# ElectricalDesign.net
KiCad netlist of a schematic drawn in Altium Designer
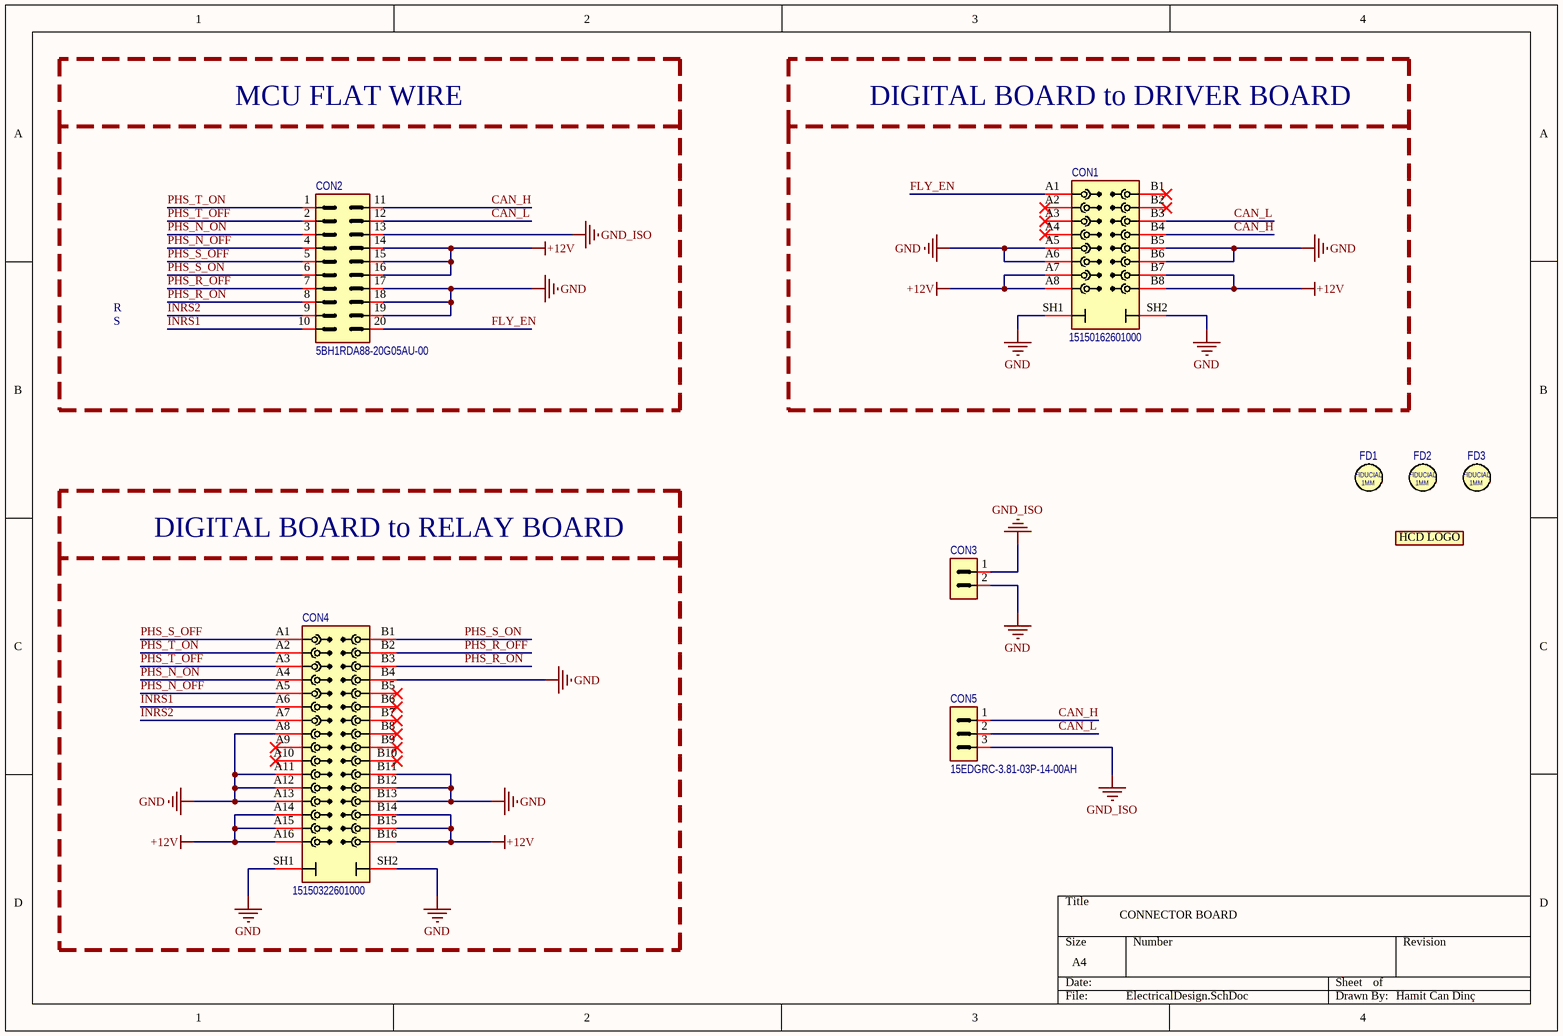
[diagram p0: ElectricalDesign.SchDoc]

(export (version "E")
  (design (tool "Eeschema 10.0.6"))
  (components
    (comp (ref "CON1")
      (value "CON_16P_2R_A8-B8_2SH")
      (footprint "CON_15150162601000_HARTING")
      (description "Connector Header Surface Mount, Right Angle 16 position 0.050\" (1.27mm)")
      (fields (field (name "MANUFACTURER PN") "15150162601000") (field (name "MANUFACTURER") "HARTING"))
      (libsource (lib "HCD_Database_Libs") (part "CON_16P_2R_A8-B8_2SH"))
    )
    (comp (ref "CON2")
      (value "CON_20POS_2R")
      (footprint "male-thd-box-header-2x10-2.54mm-90D_AMTEK")
      (description "BOX HEADER 20PIN(2x10) 2.54mm THT R/A MALE BLACK")
      (fields
        (field (name "MANUFACTURER PN") "5BH1RDA88-20G05AU-00")
        (field (name "MANUFACTURER") "AMTEK")
        (field (name "VOLTAGE") "1000V AC")
      )
      (libsource (lib "HCD_Database_Libs") (part "CON_20POS_2R"))
    )
    (comp (ref "CON3")
      (value "CON_2POS_1R")
      (footprint "male-thd-1x2-pin-header-2.54mm-90D")
      (description "PIN HEADER 2PIN(1x2) 2.54mm THT R/A 6X3X4.5MM")
      (fields (field (name "MANUFACTURER") "AMTEK") (field (name "VOLTAGE") "500V AC"))
      (libsource (lib "HCD_Database_Libs") (part "CON_2POS_1R"))
    )
    (comp (ref "CON4")
      (value "CON_32P_2R_A16-B16_2SH")
      (footprint "CON_15150322601000_HARTING")
      (description "Connector Header Surface Mount, Right Angle 32 position 0.050\" (1.27mm)")
      (fields (field (name "MANUFACTURER PN") "15150322601000") (field (name "MANUFACTURER") "HARTING"))
      (libsource (lib "HCD_Database_Libs") (part "CON_32P_2R_A16-B16_2SH"))
    )
    (comp (ref "CON5")
      (value "CON_3POS_1R")
      (footprint "CON_15EDGRC-3.81-03P-14-00AH")
      (description "TERM.BLK.3.81MM 3P 90C MALE GREEN CLOSED")
      (fields
        (field (name "MANUFACTURER PN") "15EDGRC-3.81-03P-14-00AH")
        (field (name "MANUFACTURER") "DEGSON")
        (field (name "VOLTAGE") "300V")
      )
      (libsource (lib "HCD_Database_Libs") (part "CON_3POS_1R"))
    )
    (comp (ref "FD1")
      (value "FIDUCIAL")
      (footprint "FIDUCIAL_1mm")
      (description "Fiducial 1mm")
      (libsource (lib "HCD_Database_Libs") (part "FIDUCIAL"))
    )
    (comp (ref "FD2")
      (value "FIDUCIAL")
      (footprint "FIDUCIAL_1mm")
      (description "Fiducial 1mm")
      (libsource (lib "HCD_Database_Libs") (part "FIDUCIAL"))
    )
    (comp (ref "FD3")
      (value "FIDUCIAL")
      (footprint "FIDUCIAL_1mm")
      (description "Fiducial 1mm")
      (libsource (lib "HCD_Database_Libs") (part "FIDUCIAL"))
    )
    (comp (ref "LOGO1")
      (value "HCD_LOGO")
      (footprint "HCD_LOGO_V1")
      (description "Hamit Can Dinç LOGO")
      (libsource (lib "HCD_Database_Libs") (part "HCD_LOGO"))
    )
  )
  (nets
    (net (code "1") (name "+12V") (class "Default")
      (node (ref "CON1") (pin "A7") (pinfunction "A7_A7") (pintype "passive"))
      (node (ref "CON1") (pin "A8") (pinfunction "A8_A8") (pintype "passive"))
      (node (ref "CON1") (pin "B7") (pinfunction "B7_B7") (pintype "passive"))
      (node (ref "CON1") (pin "B8") (pinfunction "B8_B8") (pintype "passive"))
      (node (ref "CON2") (pin "14") (pinfunction "14_14") (pintype "passive"))
      (node (ref "CON2") (pin "15") (pinfunction "15_15") (pintype "passive"))
      (node (ref "CON2") (pin "16") (pinfunction "16_16") (pintype "passive"))
      (node (ref "CON4") (pin "A14") (pinfunction "A14_A14") (pintype "passive"))
      (node (ref "CON4") (pin "A15") (pinfunction "A15_A15") (pintype "passive"))
      (node (ref "CON4") (pin "A16") (pinfunction "A16_A16") (pintype "passive"))
      (node (ref "CON4") (pin "B14") (pinfunction "B14_B14") (pintype "passive"))
      (node (ref "CON4") (pin "B15") (pinfunction "B15_B15") (pintype "passive"))
      (node (ref "CON4") (pin "B16") (pinfunction "B16_B16") (pintype "passive"))
    )
    (net (code "2") (name "/CAN_H") (class "Default")
      (node (ref "CON1") (pin "B4") (pinfunction "B4_B4") (pintype "passive"))
      (node (ref "CON2") (pin "11") (pinfunction "11_11") (pintype "passive"))
      (node (ref "CON5") (pin "1") (pinfunction "1_1") (pintype "passive"))
    )
    (net (code "3") (name "/CAN_L") (class "Default")
      (node (ref "CON1") (pin "B3") (pinfunction "B3_B3") (pintype "passive"))
      (node (ref "CON2") (pin "12") (pinfunction "12_12") (pintype "passive"))
      (node (ref "CON5") (pin "2") (pinfunction "2_2") (pintype "passive"))
    )
    (net (code "4") (name "/FLY_EN") (class "Default")
      (node (ref "CON1") (pin "A1") (pinfunction "A1_A1") (pintype "passive"))
      (node (ref "CON2") (pin "20") (pinfunction "20_20") (pintype "passive"))
    )
    (net (code "5") (name "/INRS1") (class "Default")
      (node (ref "CON2") (pin "10") (pinfunction "10_10") (pintype "passive"))
      (node (ref "CON4") (pin "A6") (pinfunction "A6_A6") (pintype "passive"))
    )
    (net (code "6") (name "/INRS2") (class "Default")
      (node (ref "CON2") (pin "9") (pinfunction "9_9") (pintype "passive"))
      (node (ref "CON4") (pin "A7") (pinfunction "A7_A7") (pintype "passive"))
    )
    (net (code "7") (name "/PHS_N_OFF") (class "Default")
      (node (ref "CON2") (pin "4") (pinfunction "4_4") (pintype "passive"))
      (node (ref "CON4") (pin "A5") (pinfunction "A5_A5") (pintype "passive"))
    )
    (net (code "8") (name "/PHS_N_ON") (class "Default")
      (node (ref "CON2") (pin "3") (pinfunction "3_3") (pintype "passive"))
      (node (ref "CON4") (pin "A4") (pinfunction "A4_A4") (pintype "passive"))
    )
    (net (code "9") (name "/PHS_R_OFF") (class "Default")
      (node (ref "CON2") (pin "7") (pinfunction "7_7") (pintype "passive"))
      (node (ref "CON4") (pin "B2") (pinfunction "B2_B2") (pintype "passive"))
    )
    (net (code "10") (name "/PHS_R_ON") (class "Default")
      (node (ref "CON2") (pin "8") (pinfunction "8_8") (pintype "passive"))
      (node (ref "CON4") (pin "B3") (pinfunction "B3_B3") (pintype "passive"))
    )
    (net (code "11") (name "/PHS_S_OFF") (class "Default")
      (node (ref "CON2") (pin "5") (pinfunction "5_5") (pintype "passive"))
      (node (ref "CON4") (pin "A1") (pinfunction "A1_A1") (pintype "passive"))
    )
    (net (code "12") (name "/PHS_S_ON") (class "Default")
      (node (ref "CON2") (pin "6") (pinfunction "6_6") (pintype "passive"))
      (node (ref "CON4") (pin "B1") (pinfunction "B1_B1") (pintype "passive"))
    )
    (net (code "13") (name "/PHS_T_OFF") (class "Default")
      (node (ref "CON2") (pin "2") (pinfunction "2_2") (pintype "passive"))
      (node (ref "CON4") (pin "A3") (pinfunction "A3_A3") (pintype "passive"))
    )
    (net (code "14") (name "/PHS_T_ON") (class "Default")
      (node (ref "CON2") (pin "1") (pinfunction "1_1") (pintype "passive"))
      (node (ref "CON4") (pin "A2") (pinfunction "A2_A2") (pintype "passive"))
    )
    (net (code "15") (name "GND") (class "Default")
      (node (ref "CON1") (pin "A5") (pinfunction "A5_A5") (pintype "passive"))
      (node (ref "CON1") (pin "A6") (pinfunction "A6_A6") (pintype "passive"))
      (node (ref "CON1") (pin "B5") (pinfunction "B5_B5") (pintype "passive"))
      (node (ref "CON1") (pin "B6") (pinfunction "B6_B6") (pintype "passive"))
      (node (ref "CON1") (pin "SH1") (pinfunction "SH1_SH1") (pintype "passive"))
      (node (ref "CON1") (pin "SH2") (pinfunction "SH2_SH2") (pintype "passive"))
      (node (ref "CON2") (pin "17") (pinfunction "17_17") (pintype "passive"))
      (node (ref "CON2") (pin "18") (pinfunction "18_18") (pintype "passive"))
      (node (ref "CON2") (pin "19") (pinfunction "19_19") (pintype "passive"))
      (node (ref "CON3") (pin "2") (pinfunction "2_2") (pintype "passive"))
      (node (ref "CON4") (pin "A11") (pinfunction "A11_A11") (pintype "passive"))
      (node (ref "CON4") (pin "A12") (pinfunction "A12_A12") (pintype "passive"))
      (node (ref "CON4") (pin "A13") (pinfunction "A13_A13") (pintype "passive"))
      (node (ref "CON4") (pin "A8") (pinfunction "A8_A8") (pintype "passive"))
      (node (ref "CON4") (pin "B11") (pinfunction "B11_B11") (pintype "passive"))
      (node (ref "CON4") (pin "B12") (pinfunction "B12_B12") (pintype "passive"))
      (node (ref "CON4") (pin "B13") (pinfunction "B13_B13") (pintype "passive"))
      (node (ref "CON4") (pin "B4") (pinfunction "B4_B4") (pintype "passive"))
      (node (ref "CON4") (pin "SH1") (pinfunction "SH1_SH1") (pintype "passive"))
      (node (ref "CON4") (pin "SH2") (pinfunction "SH2_SH2") (pintype "passive"))
    )
    (net (code "16") (name "GND_ISO") (class "Default")
      (node (ref "CON2") (pin "13") (pinfunction "13_13") (pintype "passive"))
      (node (ref "CON3") (pin "1") (pinfunction "1_1") (pintype "passive"))
      (node (ref "CON5") (pin "3") (pinfunction "3_3") (pintype "passive"))
    )
    (net (code "17") (name "unconnected-(CON1-PadA2)") (class "Default")
      (node (ref "CON1") (pin "A2") (pinfunction "A2_A2") (pintype "passive+no_connect"))
    )
    (net (code "18") (name "unconnected-(CON1-PadA3)") (class "Default")
      (node (ref "CON1") (pin "A3") (pinfunction "A3_A3") (pintype "passive+no_connect"))
    )
    (net (code "19") (name "unconnected-(CON1-PadA4)") (class "Default")
      (node (ref "CON1") (pin "A4") (pinfunction "A4_A4") (pintype "passive+no_connect"))
    )
    (net (code "20") (name "unconnected-(CON1-PadB1)") (class "Default")
      (node (ref "CON1") (pin "B1") (pinfunction "B1_B1") (pintype "passive+no_connect"))
    )
    (net (code "21") (name "unconnected-(CON1-PadB2)") (class "Default")
      (node (ref "CON1") (pin "B2") (pinfunction "B2_B2") (pintype "passive+no_connect"))
    )
    (net (code "22") (name "unconnected-(CON4-PadA9)") (class "Default")
      (node (ref "CON4") (pin "A9") (pinfunction "A9_A9") (pintype "passive+no_connect"))
    )
    (net (code "23") (name "unconnected-(CON4-PadA10)") (class "Default")
      (node (ref "CON4") (pin "A10") (pinfunction "A10_A10") (pintype "passive+no_connect"))
    )
    (net (code "24") (name "unconnected-(CON4-PadB5)") (class "Default")
      (node (ref "CON4") (pin "B5") (pinfunction "B5_B5") (pintype "passive+no_connect"))
    )
    (net (code "25") (name "unconnected-(CON4-PadB6)") (class "Default")
      (node (ref "CON4") (pin "B6") (pinfunction "B6_B6") (pintype "passive+no_connect"))
    )
    (net (code "26") (name "unconnected-(CON4-PadB7)") (class "Default")
      (node (ref "CON4") (pin "B7") (pinfunction "B7_B7") (pintype "passive+no_connect"))
    )
    (net (code "27") (name "unconnected-(CON4-PadB8)") (class "Default")
      (node (ref "CON4") (pin "B8") (pinfunction "B8_B8") (pintype "passive+no_connect"))
    )
    (net (code "28") (name "unconnected-(CON4-PadB9)") (class "Default")
      (node (ref "CON4") (pin "B9") (pinfunction "B9_B9") (pintype "passive+no_connect"))
    )
    (net (code "29") (name "unconnected-(CON4-PadB10)") (class "Default")
      (node (ref "CON4") (pin "B10") (pinfunction "B10_B10") (pintype "passive+no_connect"))
    )
  )
)
